# main1.net
KiCad netlist of a schematic drawn in EAGLE
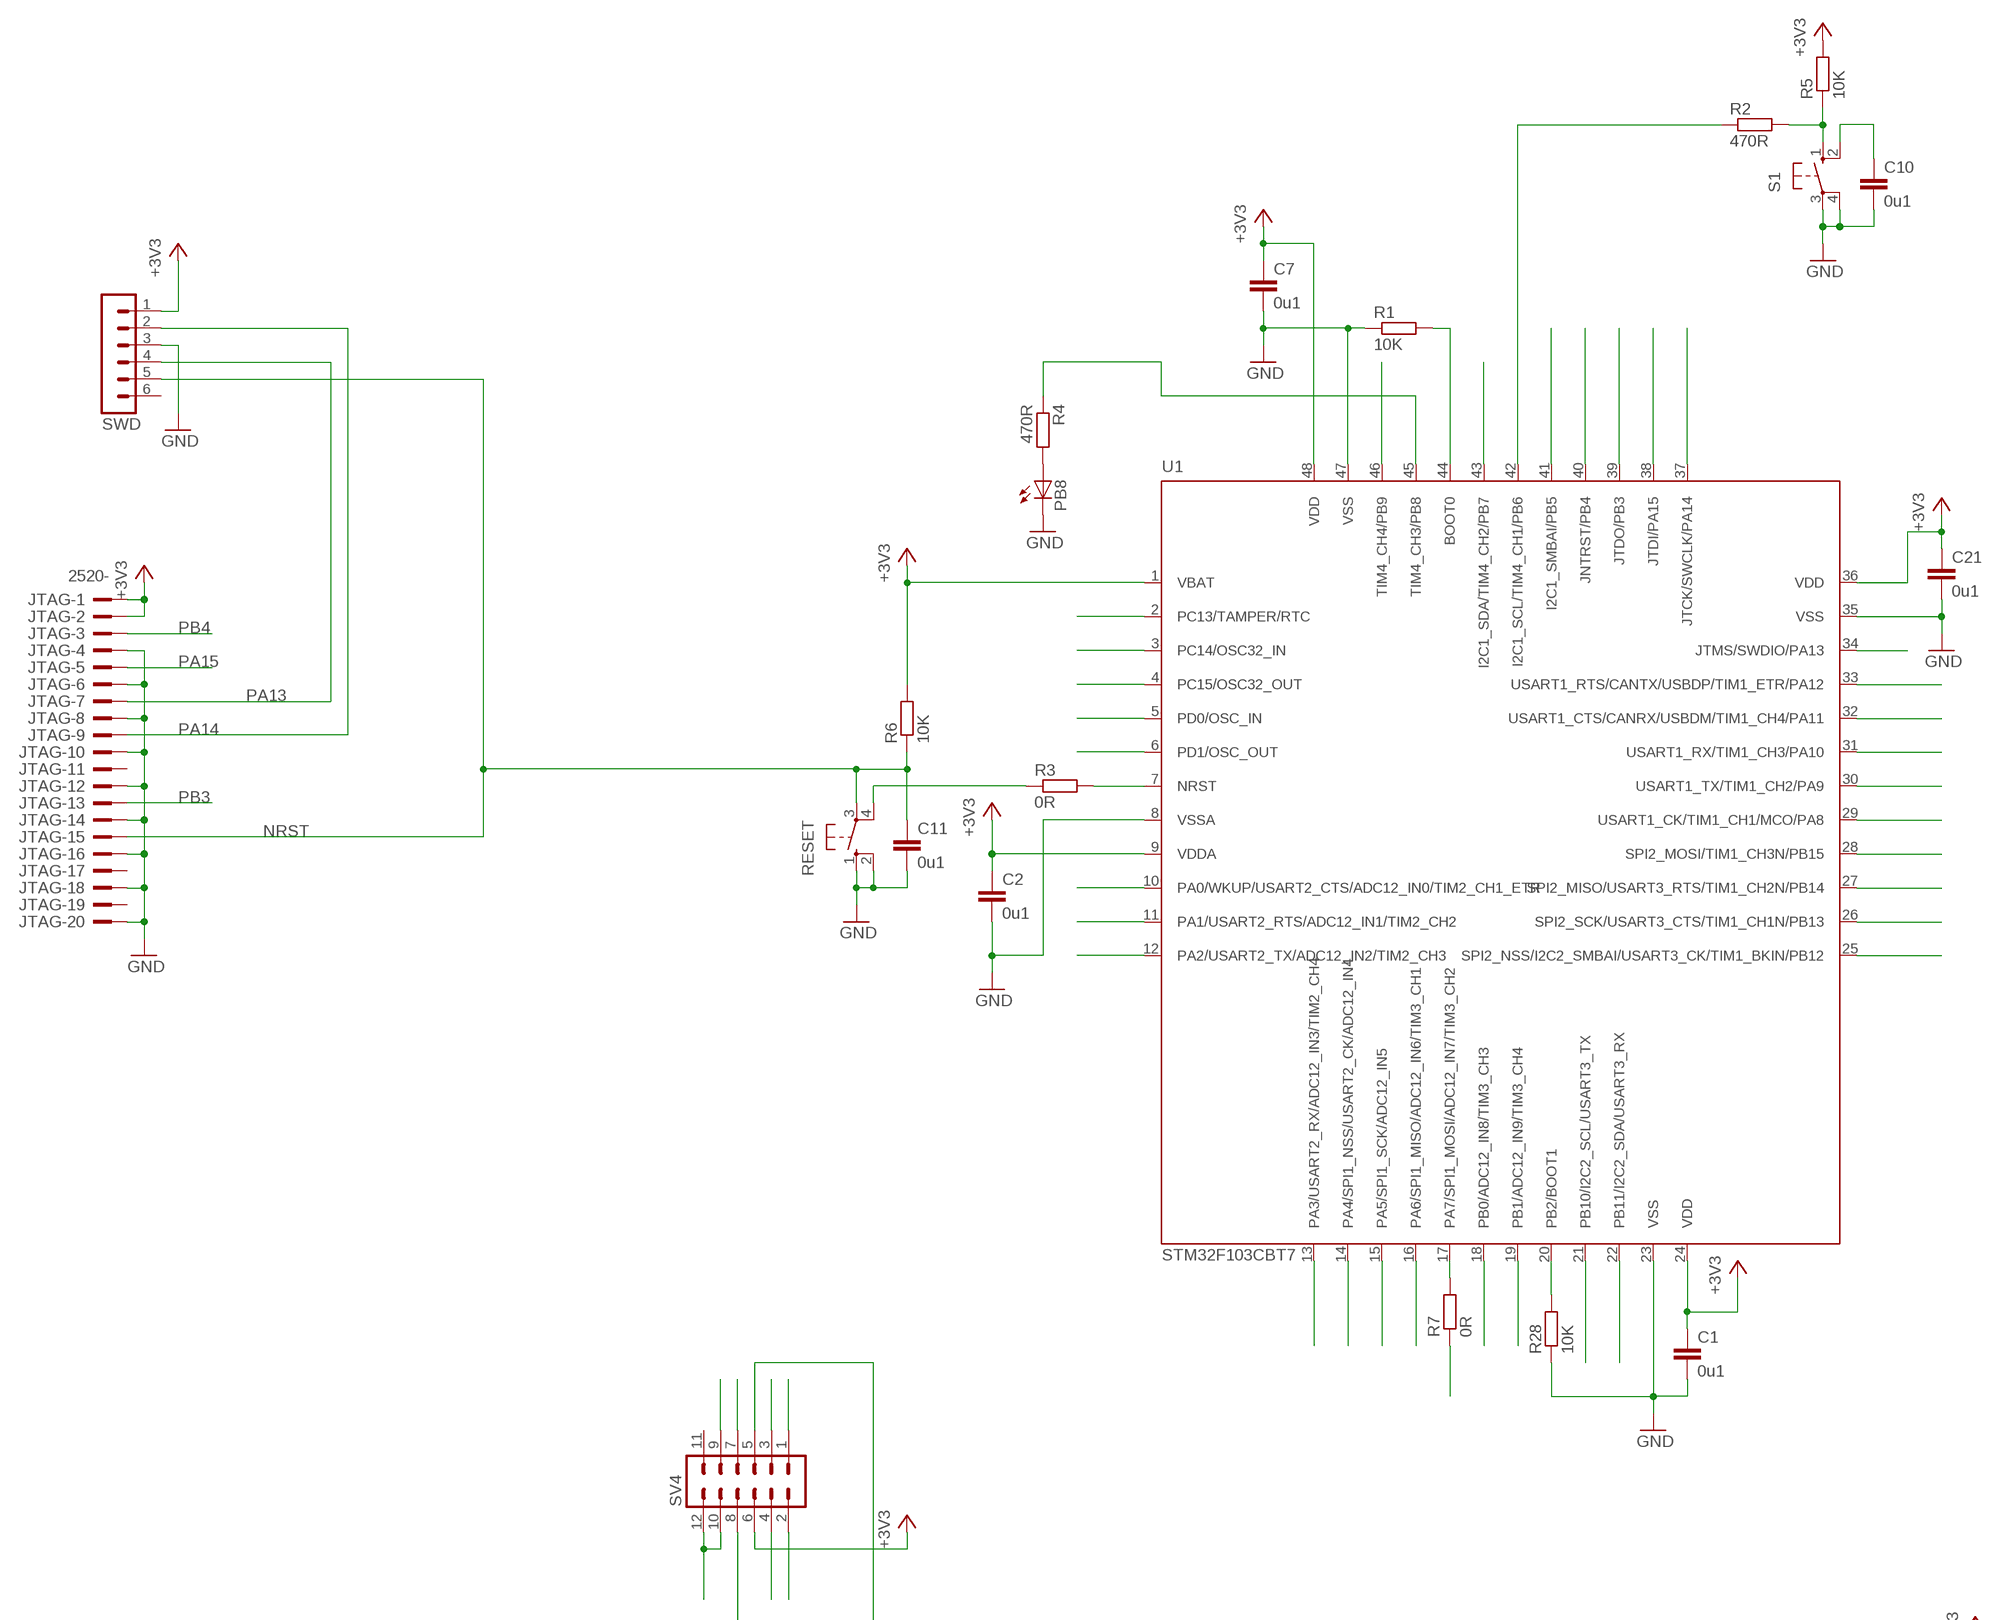
[diagram p0: schematic, sheet 1, part 1 of 2]
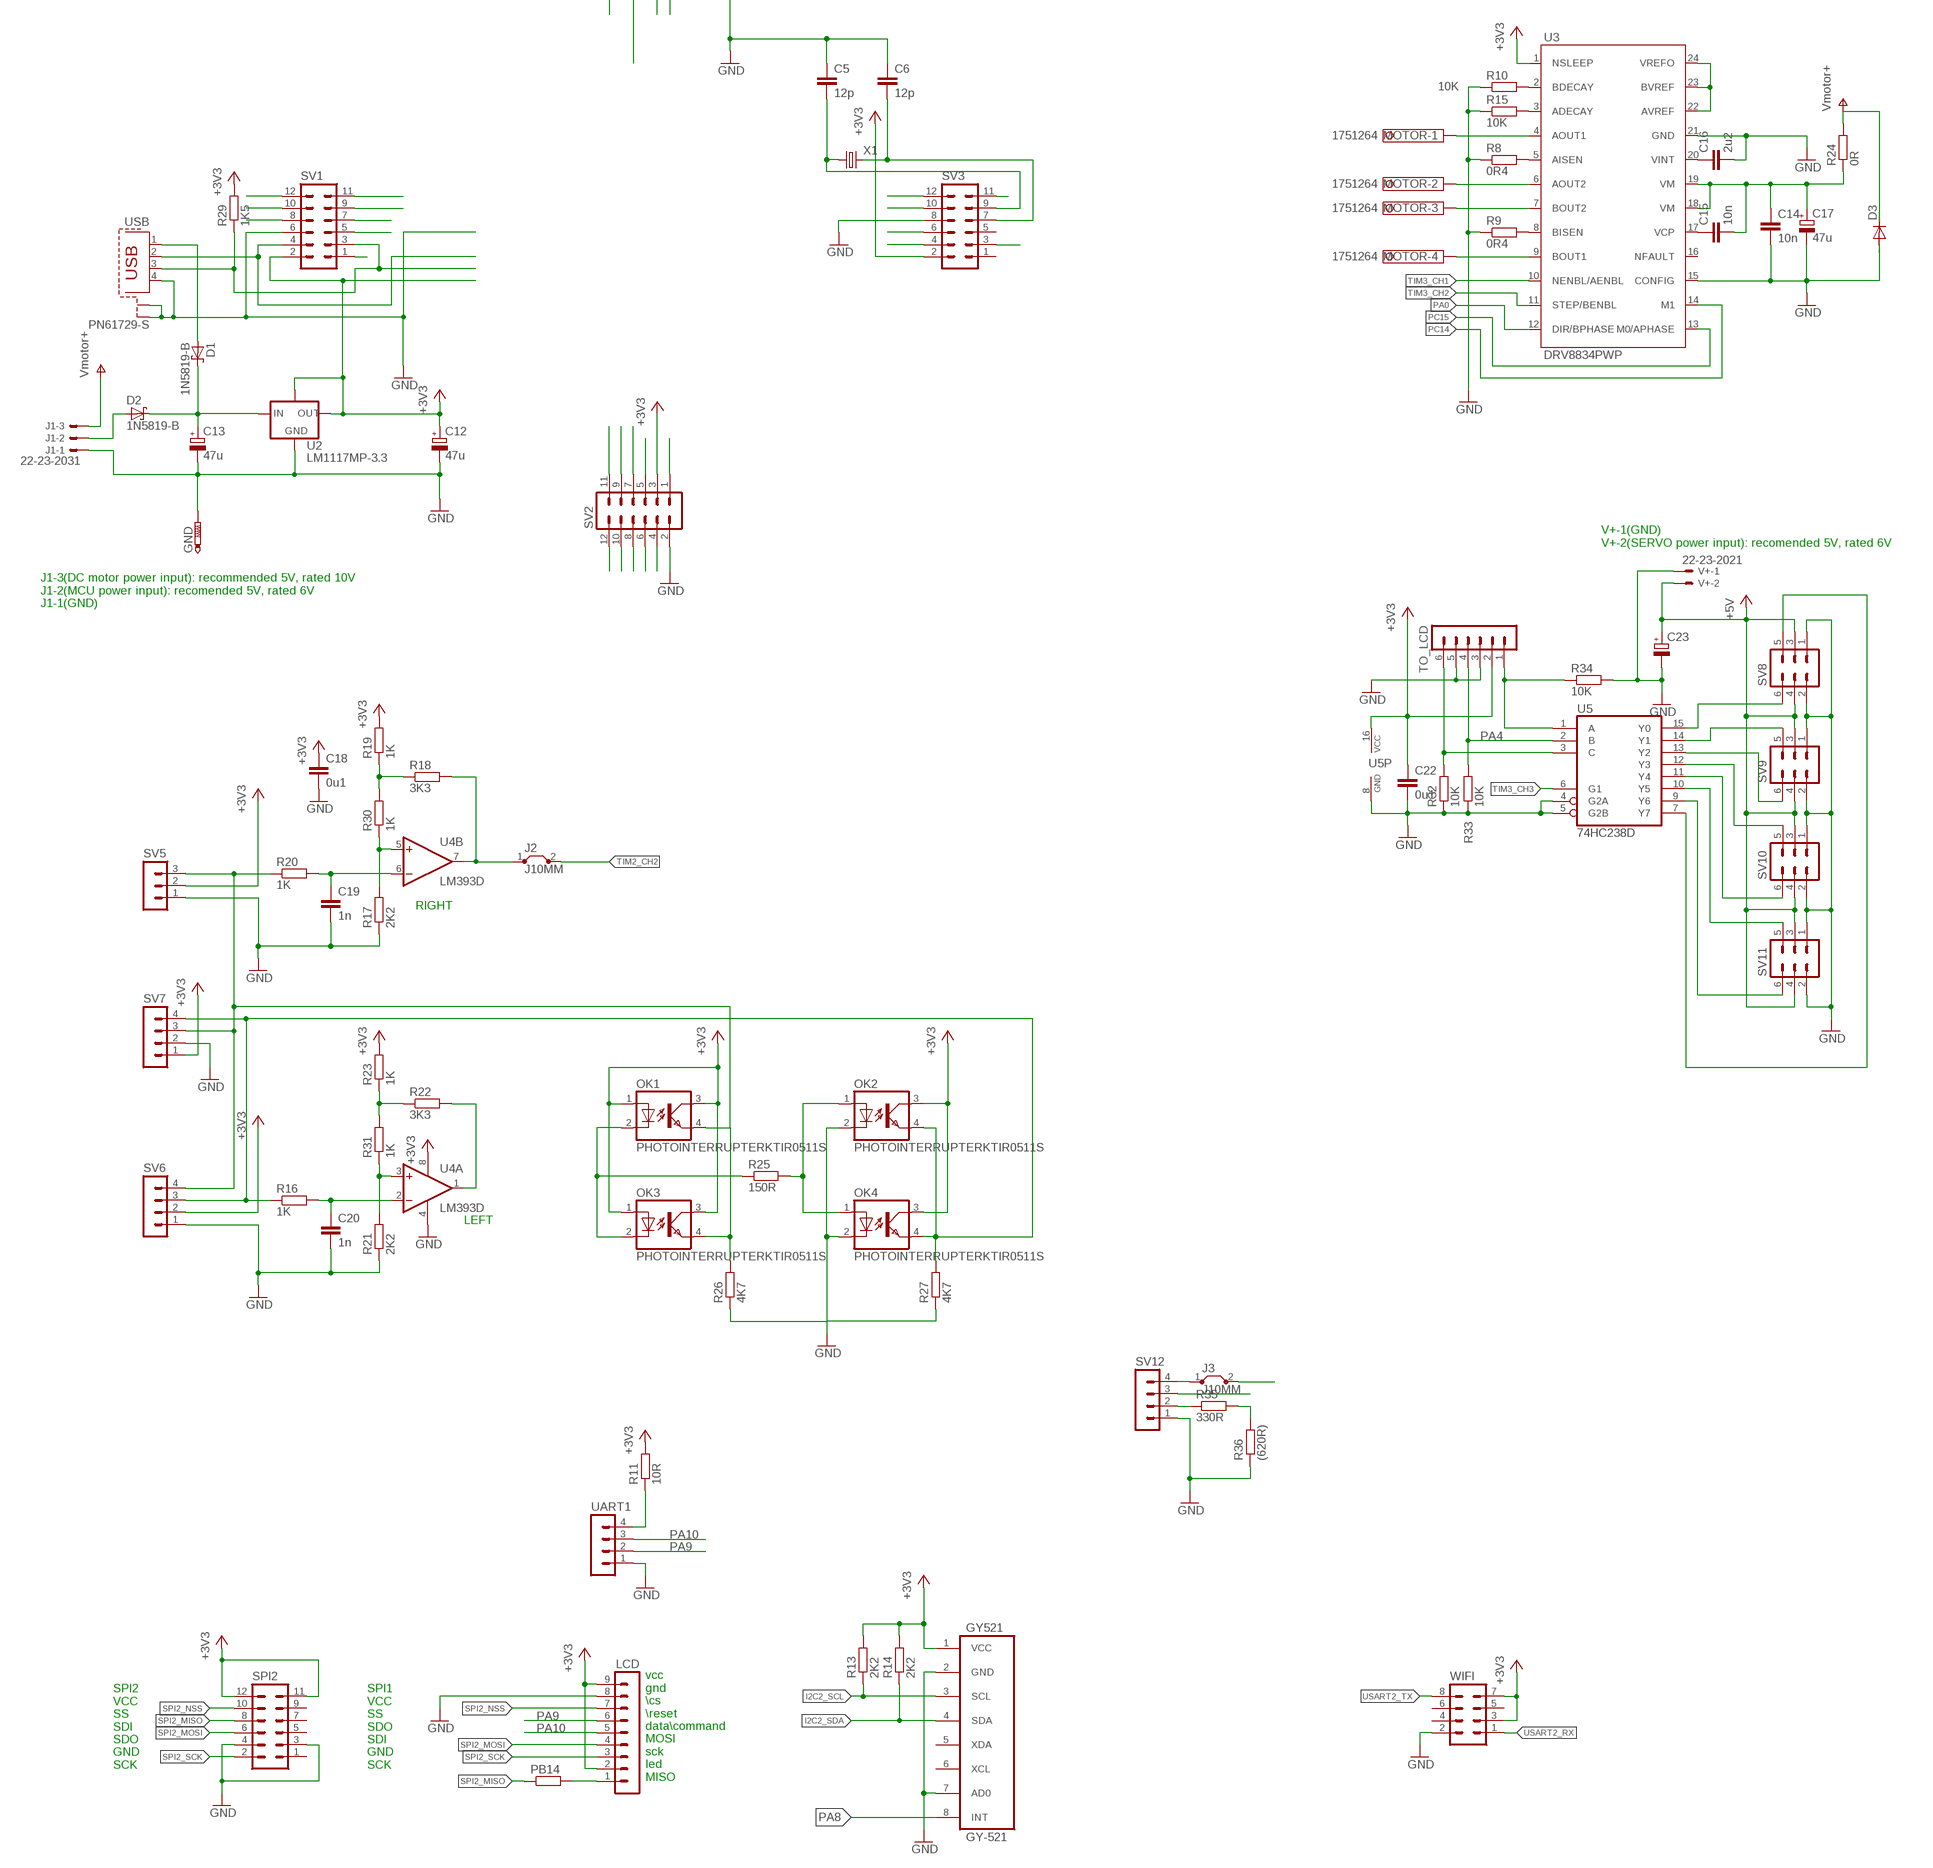
[diagram p1: schematic, sheet 1, part 2 of 2]

(export (version "E")
  (design (tool "Eeschema 10.0.6"))
  (components
    (comp (ref "C1")
      (value "0u1")
      (footprint "eagle-import:C0805")
      (libsource (lib "eagle-import") (part "C-EUC0805"))
    )
    (comp (ref "C2")
      (value "0u1")
      (footprint "eagle-import:C0805")
      (libsource (lib "eagle-import") (part "C-EUC0805"))
    )
    (comp (ref "C5")
      (value "12p")
      (footprint "eagle-import:C0805")
      (libsource (lib "eagle-import") (part "C-EUC0805"))
    )
    (comp (ref "C6")
      (value "12p")
      (footprint "eagle-import:C0805")
      (libsource (lib "eagle-import") (part "C-EUC0805"))
    )
    (comp (ref "C7")
      (value "0u1")
      (footprint "eagle-import:C0805")
      (libsource (lib "eagle-import") (part "C-EUC0805"))
    )
    (comp (ref "C10")
      (value "0u1")
      (footprint "eagle-import:C0805")
      (libsource (lib "eagle-import") (part "C-EUC0805"))
    )
    (comp (ref "C11")
      (value "0u1")
      (footprint "eagle-import:C0805")
      (libsource (lib "eagle-import") (part "C-EUC0805"))
    )
    (comp (ref "C12")
      (value "47u")
      (footprint "eagle-import:E1,8-4")
      (libsource (lib "eagle-import") (part "CPOL-EUE1.8-4"))
    )
    (comp (ref "C13")
      (value "47u")
      (footprint "eagle-import:E1,8-4")
      (libsource (lib "eagle-import") (part "CPOL-EUE1.8-4"))
    )
    (comp (ref "C14")
      (value "10n")
      (footprint "eagle-import:C0805")
      (libsource (lib "eagle-import") (part "C-EUC0805"))
    )
    (comp (ref "C15")
      (value "10n")
      (footprint "eagle-import:C0805")
      (libsource (lib "eagle-import") (part "C-EUC0805"))
    )
    (comp (ref "C16")
      (value "2u2")
      (footprint "eagle-import:C0805")
      (libsource (lib "eagle-import") (part "C-EUC0805"))
    )
    (comp (ref "C17")
      (value "47u")
      (footprint "eagle-import:E1,8-4")
      (libsource (lib "eagle-import") (part "CPOL-EUE1.8-4"))
    )
    (comp (ref "C18")
      (value "0u1")
      (footprint "eagle-import:C0805")
      (libsource (lib "eagle-import") (part "C-EUC0805"))
    )
    (comp (ref "C19")
      (value "1n")
      (footprint "eagle-import:C0805")
      (libsource (lib "eagle-import") (part "C-EUC0805"))
    )
    (comp (ref "C20")
      (value "1n")
      (footprint "eagle-import:C0805")
      (libsource (lib "eagle-import") (part "C-EUC0805"))
    )
    (comp (ref "C21")
      (value "0u1")
      (footprint "eagle-import:C0805")
      (libsource (lib "eagle-import") (part "C-EUC0805"))
    )
    (comp (ref "C22")
      (value "0u1")
      (footprint "eagle-import:C0805")
      (libsource (lib "eagle-import") (part "C-EUC0805"))
    )
    (comp (ref "C23")
      (value "CPOL-EUE2.5-7")
      (footprint "eagle-import:E2,5-7")
      (libsource (lib "eagle-import") (part "CPOL-EUE2.5-7"))
    )
    (comp (ref "D1")
      (value "1N5819-B")
      (footprint "eagle-import:DO41-7.6")
      (libsource (lib "eagle-import") (part "1N5819-B"))
    )
    (comp (ref "D2")
      (value "1N5819-B")
      (footprint "eagle-import:DO41-7.6")
      (libsource (lib "eagle-import") (part "1N5819-B"))
    )
    (comp (ref "D3")
      (value "DIODE-SMB")
      (footprint "eagle-import:SMB")
      (libsource (lib "eagle-import") (part "DIODE-SMB"))
    )
    (comp (ref "GND")
      (value "PTR1PAD1-13")
      (footprint "eagle-import:P1-13")
      (libsource (lib "eagle-import") (part "PTR1PAD1-13"))
    )
    (comp (ref "GY521")
      (value "GY-521")
      (footprint "eagle-import:GY-521")
      (libsource (lib "eagle-import") (part "GY-521"))
    )
    (comp (ref "J1")
      (value "22-23-2031")
      (footprint "eagle-import:22-23-2031")
      (fields (field (name "MF") "MOLEX"))
      (libsource (lib "eagle-import") (part "22-23-2031"))
    )
    (comp (ref "J2")
      (value "J10MM")
      (footprint "eagle-import:10")
      (libsource (lib "eagle-import") (part "J10MM"))
    )
    (comp (ref "J3")
      (value "J10MM")
      (footprint "eagle-import:10")
      (libsource (lib "eagle-import") (part "J10MM"))
    )
    (comp (ref "JTAG")
      (value "2520-")
      (footprint "eagle-import:PAK100_2500-20")
      (libsource (lib "eagle-import") (part "2520-"))
    )
    (comp (ref "LCD")
      (value "MA09-1")
      (footprint "eagle-import:MA09-1")
      (libsource (lib "eagle-import") (part "MA09-1"))
    )
    (comp (ref "MOTOR")
      (value "1751264")
      (footprint "eagle-import:1751264")
      (libsource (lib "eagle-import") (part "1751264"))
    )
    (comp (ref "OK1")
      (value "PHOTOINTERRUPTERKTIR0511S")
      (footprint "eagle-import:KTIR0511S")
      (libsource (lib "eagle-import") (part "PHOTOINTERRUPTERKTIR0511S"))
    )
    (comp (ref "OK2")
      (value "PHOTOINTERRUPTERKTIR0511S")
      (footprint "eagle-import:KTIR0511S")
      (libsource (lib "eagle-import") (part "PHOTOINTERRUPTERKTIR0511S"))
    )
    (comp (ref "OK3")
      (value "PHOTOINTERRUPTERKTIR0511S")
      (footprint "eagle-import:KTIR0511S")
      (libsource (lib "eagle-import") (part "PHOTOINTERRUPTERKTIR0511S"))
    )
    (comp (ref "OK4")
      (value "PHOTOINTERRUPTERKTIR0511S")
      (footprint "eagle-import:KTIR0511S")
      (libsource (lib "eagle-import") (part "PHOTOINTERRUPTERKTIR0511S"))
    )
    (comp (ref "PB8")
      (value "LED3MM")
      (footprint "eagle-import:LED3MM")
      (libsource (lib "eagle-import") (part "LED3MM"))
    )
    (comp (ref "PB14")
      (value "R-EU_0207/10")
      (footprint "eagle-import:0207_10")
      (libsource (lib "eagle-import") (part "R-EU_0207/10"))
    )
    (comp (ref "R1")
      (value "10K")
      (footprint "eagle-import:M0805")
      (libsource (lib "eagle-import") (part "R-EU_M0805"))
    )
    (comp (ref "R2")
      (value "470R")
      (footprint "eagle-import:0207_10")
      (libsource (lib "eagle-import") (part "R-EU_0207/10"))
    )
    (comp (ref "R3")
      (value "0R")
      (footprint "eagle-import:0207_10")
      (libsource (lib "eagle-import") (part "R-EU_0207/10"))
    )
    (comp (ref "R4")
      (value "470R")
      (footprint "eagle-import:0207_10")
      (libsource (lib "eagle-import") (part "R-EU_0207/10"))
    )
    (comp (ref "R5")
      (value "10K")
      (footprint "eagle-import:0207_10")
      (libsource (lib "eagle-import") (part "R-EU_0207/10"))
    )
    (comp (ref "R6")
      (value "10K")
      (footprint "eagle-import:M0805")
      (libsource (lib "eagle-import") (part "R-EU_M0805"))
    )
    (comp (ref "R7")
      (value "0R")
      (footprint "eagle-import:0207_10")
      (libsource (lib "eagle-import") (part "R-EU_0207/10"))
    )
    (comp (ref "R8")
      (value "0R4")
      (footprint "eagle-import:R2010")
      (libsource (lib "eagle-import") (part "R-EU_R2010"))
    )
    (comp (ref "R9")
      (value "0R4")
      (footprint "eagle-import:R2010")
      (libsource (lib "eagle-import") (part "R-EU_R2010"))
    )
    (comp (ref "R10")
      (value "10K")
      (footprint "eagle-import:R0805")
      (libsource (lib "eagle-import") (part "R-EU_R0805"))
    )
    (comp (ref "R11")
      (value "10R")
      (footprint "eagle-import:M0805")
      (libsource (lib "eagle-import") (part "R-EU_M0805"))
    )
    (comp (ref "R13")
      (value "2K2")
      (footprint "eagle-import:M0805")
      (libsource (lib "eagle-import") (part "R-EU_M0805"))
    )
    (comp (ref "R14")
      (value "2K2")
      (footprint "eagle-import:M0805")
      (libsource (lib "eagle-import") (part "R-EU_M0805"))
    )
    (comp (ref "R15")
      (value "10K")
      (footprint "eagle-import:R0805")
      (libsource (lib "eagle-import") (part "R-EU_R0805"))
    )
    (comp (ref "R16")
      (value "1K")
      (footprint "eagle-import:0207_10")
      (libsource (lib "eagle-import") (part "R-EU_0207/10"))
    )
    (comp (ref "R17")
      (value "2K2")
      (footprint "eagle-import:M0805")
      (libsource (lib "eagle-import") (part "R-EU_M0805"))
    )
    (comp (ref "R18")
      (value "3K3")
      (footprint "eagle-import:M0805")
      (libsource (lib "eagle-import") (part "R-EU_M0805"))
    )
    (comp (ref "R19")
      (value "1K")
      (footprint "eagle-import:M0805")
      (libsource (lib "eagle-import") (part "R-EU_M0805"))
    )
    (comp (ref "R20")
      (value "1K")
      (footprint "eagle-import:0207_10")
      (libsource (lib "eagle-import") (part "R-EU_0207/10"))
    )
    (comp (ref "R21")
      (value "2K2")
      (footprint "eagle-import:M0805")
      (libsource (lib "eagle-import") (part "R-EU_M0805"))
    )
    (comp (ref "R22")
      (value "3K3")
      (footprint "eagle-import:M0805")
      (libsource (lib "eagle-import") (part "R-EU_M0805"))
    )
    (comp (ref "R23")
      (value "1K")
      (footprint "eagle-import:M0805")
      (libsource (lib "eagle-import") (part "R-EU_M0805"))
    )
    (comp (ref "R24")
      (value "0R")
      (footprint "eagle-import:0207_10")
      (libsource (lib "eagle-import") (part "R-EU_0207/10"))
    )
    (comp (ref "R25")
      (value "150R")
      (footprint "eagle-import:0207_10")
      (libsource (lib "eagle-import") (part "R-EU_0207/10"))
    )
    (comp (ref "R26")
      (value "4K7")
      (footprint "eagle-import:M0805")
      (libsource (lib "eagle-import") (part "R-EU_M0805"))
    )
    (comp (ref "R27")
      (value "4K7")
      (footprint "eagle-import:M0805")
      (libsource (lib "eagle-import") (part "R-EU_M0805"))
    )
    (comp (ref "R28")
      (value "10K")
      (footprint "eagle-import:M0805")
      (libsource (lib "eagle-import") (part "R-EU_M0805"))
    )
    (comp (ref "R29")
      (value "1K5")
      (footprint "eagle-import:M0805")
      (libsource (lib "eagle-import") (part "R-EU_M0805"))
    )
    (comp (ref "R30")
      (value "1K")
      (footprint "eagle-import:M0805")
      (libsource (lib "eagle-import") (part "R-EU_M0805"))
    )
    (comp (ref "R31")
      (value "1K")
      (footprint "eagle-import:M0805")
      (libsource (lib "eagle-import") (part "R-EU_M0805"))
    )
    (comp (ref "R32")
      (value "10K")
      (footprint "eagle-import:M0805")
      (libsource (lib "eagle-import") (part "R-EU_M0805"))
    )
    (comp (ref "R33")
      (value "10K")
      (footprint "eagle-import:M0805")
      (libsource (lib "eagle-import") (part "R-EU_M0805"))
    )
    (comp (ref "R34")
      (value "10K")
      (footprint "eagle-import:M0805")
      (libsource (lib "eagle-import") (part "R-EU_M0805"))
    )
    (comp (ref "R35")
      (value "330R")
      (footprint "eagle-import:M0805")
      (libsource (lib "eagle-import") (part "R-EU_M0805"))
    )
    (comp (ref "R36")
      (value "(620R)")
      (footprint "eagle-import:M0805")
      (libsource (lib "eagle-import") (part "R-EU_M0805"))
    )
    (comp (ref "RESET")
      (value "10-XX")
      (footprint "eagle-import:B3F-10XX")
      (fields (field (name "MPN") "B3F-1000"))
      (libsource (lib "eagle-import") (part "10-XX"))
    )
    (comp (ref "S1")
      (value "10-XX")
      (footprint "eagle-import:B3F-10XX")
      (fields (field (name "MPN") "B3F-1000"))
      (libsource (lib "eagle-import") (part "10-XX"))
    )
    (comp (ref "SPI2")
      (value "MA06-2")
      (footprint "eagle-import:MA06-2")
      (libsource (lib "eagle-import") (part "MA06-2"))
    )
    (comp (ref "SV1")
      (value "MA06-2")
      (footprint "eagle-import:MA06-2")
      (libsource (lib "eagle-import") (part "MA06-2"))
    )
    (comp (ref "SV2")
      (value "MA06-2")
      (footprint "eagle-import:MA06-2")
      (libsource (lib "eagle-import") (part "MA06-2"))
    )
    (comp (ref "SV3")
      (value "MA06-2")
      (footprint "eagle-import:MA06-2")
      (libsource (lib "eagle-import") (part "MA06-2"))
    )
    (comp (ref "SV4")
      (value "MA06-2")
      (footprint "eagle-import:MA06-2")
      (libsource (lib "eagle-import") (part "MA06-2"))
    )
    (comp (ref "SV5")
      (value "MA03-1")
      (footprint "eagle-import:MA03-1")
      (libsource (lib "eagle-import") (part "MA03-1"))
    )
    (comp (ref "SV6")
      (value "MA04-1")
      (footprint "eagle-import:MA04-1")
      (libsource (lib "eagle-import") (part "MA04-1"))
    )
    (comp (ref "SV7")
      (value "MA04-1")
      (footprint "eagle-import:MA04-1")
      (libsource (lib "eagle-import") (part "MA04-1"))
    )
    (comp (ref "SV8")
      (value "MA03-2")
      (footprint "eagle-import:MA03-2")
      (libsource (lib "eagle-import") (part "MA03-2"))
    )
    (comp (ref "SV9")
      (value "MA03-2")
      (footprint "eagle-import:MA03-2")
      (libsource (lib "eagle-import") (part "MA03-2"))
    )
    (comp (ref "SV10")
      (value "MA03-2")
      (footprint "eagle-import:MA03-2")
      (libsource (lib "eagle-import") (part "MA03-2"))
    )
    (comp (ref "SV11")
      (value "MA03-2")
      (footprint "eagle-import:MA03-2")
      (libsource (lib "eagle-import") (part "MA03-2"))
    )
    (comp (ref "SV12")
      (value "MA04-1")
      (footprint "eagle-import:MA04-1")
      (libsource (lib "eagle-import") (part "MA04-1"))
    )
    (comp (ref "SWD")
      (value "MA06-1")
      (footprint "eagle-import:MA06-1")
      (libsource (lib "eagle-import") (part "MA06-1"))
    )
    (comp (ref "TO_LCD")
      (value "MA06-1")
      (footprint "eagle-import:MA06-1")
      (libsource (lib "eagle-import") (part "MA06-1"))
    )
    (comp (ref "U1")
      (value "STM32F103CBT7")
      (footprint "eagle-import:LQFP48-7X7")
      (libsource (lib "eagle-import") (part "STM32F103CBT7"))
    )
    (comp (ref "U2")
      (value "LM1117MP-3.3")
      (footprint "eagle-import:SOT230P700X180-4N")
      (libsource (lib "eagle-import") (part "LM1117"))
    )
    (comp (ref "U3")
      (value "DRV8834PWP")
      (footprint "eagle-import:PWP-TSSOP24")
      (libsource (lib "eagle-import") (part "DRV8834PWP"))
    )
    (comp (ref "U4")
      (value "LM393D")
      (footprint "eagle-import:SO08")
      (libsource (lib "eagle-import") (part "LM393D"))
    )
    (comp (ref "U5")
      (value "74HC238D")
      (footprint "eagle-import:SO16")
      (libsource (lib "eagle-import") (part "74238DHC"))
    )
    (comp (ref "UART1")
      (value "MA04-1")
      (footprint "eagle-import:MA04-1")
      (libsource (lib "eagle-import") (part "MA04-1"))
    )
    (comp (ref "USB")
      (value "PN61729-S")
      (footprint "eagle-import:PN61729-S")
      (libsource (lib "eagle-import") (part "PN61729-S"))
    )
    (comp (ref "V+")
      (value "22-23-2021")
      (footprint "eagle-import:22-23-2021")
      (fields (field (name "MF") "MOLEX"))
      (libsource (lib "eagle-import") (part "22-23-2021"))
    )
    (comp (ref "WIFI")
      (value "MA04-2")
      (footprint "eagle-import:MA04-2")
      (libsource (lib "eagle-import") (part "MA04-2"))
    )
    (comp (ref "X1")
      (value "CRYSTALHC49S")
      (footprint "eagle-import:HC49_S")
      (libsource (lib "eagle-import") (part "CRYSTALHC49S"))
    )
  )
  (nets
    (net (code "1") (name "+3V3") (class "Default")
      (node (ref "C1") (pin "1") (pinfunction "1_1") (pintype "passive"))
      (node (ref "C12") (pin "+") (pinfunction "+_+") (pintype "passive"))
      (node (ref "C18") (pin "1") (pinfunction "1_1") (pintype "passive"))
      (node (ref "C2") (pin "1") (pinfunction "1_1") (pintype "passive"))
      (node (ref "C21") (pin "1") (pinfunction "1_1") (pintype "passive"))
      (node (ref "C22") (pin "1") (pinfunction "1_1") (pintype "passive"))
      (node (ref "C7") (pin "1") (pinfunction "1_1") (pintype "passive"))
      (node (ref "GY521") (pin "1") (pinfunction "VCC_1") (pintype "power_in"))
      (node (ref "JTAG") (pin "1") (pinfunction "KL_1") (pintype "passive"))
      (node (ref "JTAG") (pin "2") (pinfunction "KL_2") (pintype "passive"))
      (node (ref "LCD") (pin "2") (pinfunction "2_2") (pintype "passive"))
      (node (ref "LCD") (pin "9") (pinfunction "9_9") (pintype "passive"))
      (node (ref "OK1") (pin "1") (pinfunction "A_1") (pintype "passive"))
      (node (ref "OK1") (pin "3") (pinfunction "COL_3") (pintype "passive"))
      (node (ref "OK2") (pin "3") (pinfunction "COL_3") (pintype "passive"))
      (node (ref "OK3") (pin "1") (pinfunction "A_1") (pintype "passive"))
      (node (ref "OK3") (pin "3") (pinfunction "COL_3") (pintype "passive"))
      (node (ref "OK4") (pin "3") (pinfunction "COL_3") (pintype "passive"))
      (node (ref "R11") (pin "2") (pinfunction "2_2") (pintype "passive"))
      (node (ref "R13") (pin "2") (pinfunction "2_2") (pintype "passive"))
      (node (ref "R14") (pin "2") (pinfunction "2_2") (pintype "passive"))
      (node (ref "R19") (pin "2") (pinfunction "2_2") (pintype "passive"))
      (node (ref "R23") (pin "2") (pinfunction "2_2") (pintype "passive"))
      (node (ref "R29") (pin "2") (pinfunction "2_2") (pintype "passive"))
      (node (ref "R5") (pin "2") (pinfunction "2_2") (pintype "passive"))
      (node (ref "R6") (pin "2") (pinfunction "2_2") (pintype "passive"))
      (node (ref "SPI2") (pin "11") (pinfunction "11_11") (pintype "passive"))
      (node (ref "SPI2") (pin "12") (pinfunction "12_12") (pintype "passive"))
      (node (ref "SV1") (pin "2") (pinfunction "2_2") (pintype "passive"))
      (node (ref "SV2") (pin "3") (pinfunction "3_3") (pintype "passive"))
      (node (ref "SV3") (pin "2") (pinfunction "2_2") (pintype "passive"))
      (node (ref "SV4") (pin "6") (pinfunction "6_6") (pintype "passive"))
      (node (ref "SV5") (pin "2") (pinfunction "2_2") (pintype "passive"))
      (node (ref "SV6") (pin "2") (pinfunction "2_2") (pintype "passive"))
      (node (ref "SV7") (pin "1") (pinfunction "1_1") (pintype "passive"))
      (node (ref "SWD") (pin "1") (pinfunction "1_1") (pintype "passive"))
      (node (ref "TO_LCD") (pin "2") (pinfunction "2_2") (pintype "passive"))
      (node (ref "U1") (pin "1") (pinfunction "VBAT_1") (pintype "input"))
      (node (ref "U1") (pin "24") (pinfunction "VDD_24") (pintype "power_in"))
      (node (ref "U1") (pin "36") (pinfunction "VDD_36") (pintype "power_in"))
      (node (ref "U1") (pin "48") (pinfunction "VDD_48") (pintype "power_in"))
      (node (ref "U1") (pin "9") (pinfunction "VDDA_9") (pintype "power_in"))
      (node (ref "U2") (pin "2") (pinfunction "OUT_2") (pintype "passive"))
      (node (ref "U2") (pin "4") (pinfunction "TAB_4") (pintype "passive"))
      (node (ref "U3") (pin "1") (pinfunction "NSLEEP_1") (pintype "passive"))
      (node (ref "U4") (pin "8") (pinfunction "V+_8") (pintype "power_in"))
      (node (ref "U5") (pin "16") (pinfunction "VCC_16") (pintype "power_in"))
      (node (ref "WIFI") (pin "3") (pinfunction "3_3") (pintype "passive"))
      (node (ref "WIFI") (pin "7") (pinfunction "7_7") (pintype "passive"))
    )
    (net (code "2") (name "+5V") (class "Default")
      (node (ref "C23") (pin "+") (pinfunction "+_+") (pintype "passive"))
      (node (ref "SV10") (pin "3") (pinfunction "3_3") (pintype "passive"))
      (node (ref "SV10") (pin "4") (pinfunction "4_4") (pintype "passive"))
      (node (ref "SV11") (pin "3") (pinfunction "3_3") (pintype "passive"))
      (node (ref "SV11") (pin "4") (pinfunction "4_4") (pintype "passive"))
      (node (ref "SV8") (pin "3") (pinfunction "3_3") (pintype "passive"))
      (node (ref "SV8") (pin "4") (pinfunction "4_4") (pintype "passive"))
      (node (ref "SV9") (pin "3") (pinfunction "3_3") (pintype "passive"))
      (node (ref "SV9") (pin "4") (pinfunction "4_4") (pintype "passive"))
      (node (ref "V+") (pin "2") (pinfunction "S_2") (pintype "passive"))
    )
    (net (code "3") (name "/BOOT0") (class "Default")
      (node (ref "R1") (pin "2") (pinfunction "2_2") (pintype "passive"))
      (node (ref "SV2") (pin "5") (pinfunction "5_5") (pintype "passive"))
      (node (ref "U1") (pin "44") (pinfunction "BOOT0_44") (pintype "input"))
    )
    (net (code "4") (name "/BOOT1") (class "Default")
      (node (ref "R28") (pin "2") (pinfunction "2_2") (pintype "passive"))
      (node (ref "SV4") (pin "8") (pinfunction "8_8") (pintype "passive"))
      (node (ref "U1") (pin "20") (pinfunction "PB2/BOOT1_20") (pintype "bidirectional"))
    )
    (net (code "5") (name "/N$13") (class "Default")
      (node (ref "D2") (pin "A") (pinfunction "A_A") (pintype "passive"))
      (node (ref "J1") (pin "2") (pinfunction "S_2") (pintype "passive"))
      (node (ref "J3") (pin "2") (pinfunction "2_2") (pintype "passive"))
    )
    (net (code "6") (name "/NRST") (class "Default")
      (node (ref "C11") (pin "1") (pinfunction "1_1") (pintype "passive"))
      (node (ref "JTAG") (pin "15") (pinfunction "KL_15") (pintype "passive"))
      (node (ref "R6") (pin "1") (pinfunction "1_1") (pintype "passive"))
      (node (ref "RESET") (pin "3") (pinfunction "P_3") (pintype "passive"))
      (node (ref "SWD") (pin "5") (pinfunction "5_5") (pintype "passive"))
    )
    (net (code "7") (name "/PA4") (class "Default")
      (node (ref "R33") (pin "2") (pinfunction "2_2") (pintype "passive"))
      (node (ref "SV4") (pin "1") (pinfunction "1_1") (pintype "passive"))
      (node (ref "TO_LCD") (pin "4") (pinfunction "4_4") (pintype "passive"))
      (node (ref "U1") (pin "14") (pinfunction "PA4/SPI1_NSS/USART2_CK/ADC12_IN4_14") (pintype "bidirectional"))
      (node (ref "U5") (pin "2") (pinfunction "B_2") (pintype "input"))
    )
    (net (code "8") (name "/PA5") (class "Default")
      (node (ref "SV4") (pin "2") (pinfunction "2_2") (pintype "passive"))
      (node (ref "U1") (pin "15") (pinfunction "PA5/SPI1_SCK/ADC12_IN5_15") (pintype "bidirectional"))
    )
    (net (code "9") (name "/PA9") (class "Default")
      (node (ref "LCD") (pin "6") (pinfunction "6_6") (pintype "passive"))
      (node (ref "SV1") (pin "8") (pinfunction "8_8") (pintype "passive"))
      (node (ref "U1") (pin "30") (pinfunction "USART1_TX/TIM1_CH2/PA9_30") (pintype "bidirectional"))
      (node (ref "UART1") (pin "2") (pinfunction "2_2") (pintype "passive"))
    )
    (net (code "10") (name "/PA10") (class "Default")
      (node (ref "LCD") (pin "5") (pinfunction "5_5") (pintype "passive"))
      (node (ref "SV1") (pin "5") (pinfunction "5_5") (pintype "passive"))
      (node (ref "U1") (pin "31") (pinfunction "USART1_RX/TIM1_CH3/PA10_31") (pintype "bidirectional"))
      (node (ref "UART1") (pin "3") (pinfunction "3_3") (pintype "passive"))
    )
    (net (code "11") (name "/PA13") (class "Default")
      (node (ref "JTAG") (pin "7") (pinfunction "KL_7") (pintype "passive"))
      (node (ref "SV1") (pin "1") (pinfunction "1_1") (pintype "passive"))
      (node (ref "SWD") (pin "4") (pinfunction "4_4") (pintype "passive"))
      (node (ref "U1") (pin "34") (pinfunction "JTMS/SWDIO/PA13_34") (pintype "bidirectional"))
    )
    (net (code "12") (name "/PA14") (class "Default")
      (node (ref "JTAG") (pin "9") (pinfunction "KL_9") (pintype "passive"))
      (node (ref "SV2") (pin "12") (pinfunction "12_12") (pintype "passive"))
      (node (ref "SWD") (pin "2") (pinfunction "2_2") (pintype "passive"))
      (node (ref "U1") (pin "37") (pinfunction "JTCK/SWCLK/PA14_37") (pintype "bidirectional"))
    )
    (net (code "13") (name "/PA15") (class "Default")
      (node (ref "JTAG") (pin "5") (pinfunction "KL_5") (pintype "passive"))
      (node (ref "SV2") (pin "11") (pinfunction "11_11") (pintype "passive"))
      (node (ref "U1") (pin "38") (pinfunction "JTDI/PA15_38") (pintype "bidirectional"))
    )
    (net (code "14") (name "/PB1") (class "Default")
      (node (ref "SV4") (pin "7") (pinfunction "7_7") (pintype "passive"))
      (node (ref "U1") (pin "19") (pinfunction "PB1/ADC12_IN9/TIM3_CH4_19") (pintype "bidirectional"))
    )
    (net (code "15") (name "/PB3") (class "Default")
      (node (ref "JTAG") (pin "13") (pinfunction "KL_13") (pintype "passive"))
      (node (ref "SV2") (pin "10") (pinfunction "10_10") (pintype "passive"))
      (node (ref "U1") (pin "39") (pinfunction "JTDO/PB3_39") (pintype "bidirectional"))
    )
    (net (code "16") (name "/PB4") (class "Default")
      (node (ref "JTAG") (pin "3") (pinfunction "KL_3") (pintype "passive"))
      (node (ref "R35") (pin "2") (pinfunction "2_2") (pintype "passive"))
      (node (ref "R36") (pin "2") (pinfunction "2_2") (pintype "passive"))
      (node (ref "SV2") (pin "9") (pinfunction "9_9") (pintype "passive"))
      (node (ref "U1") (pin "40") (pinfunction "JNTRST/PB4_40") (pintype "bidirectional"))
    )
    (net (code "17") (name "/PB5") (class "Default")
      (node (ref "SV12") (pin "3") (pinfunction "3_3") (pintype "passive"))
      (node (ref "SV2") (pin "8") (pinfunction "8_8") (pintype "passive"))
      (node (ref "U1") (pin "41") (pinfunction "I2C1_SMBAI/PB5_41") (pintype "bidirectional"))
    )
    (net (code "18") (name "/PB6") (class "Default")
      (node (ref "R2") (pin "1") (pinfunction "1_1") (pintype "passive"))
      (node (ref "SV2") (pin "7") (pinfunction "7_7") (pintype "passive"))
      (node (ref "U1") (pin "42") (pinfunction "I2C1_SCL/TIM4_CH1/PB6_42") (pintype "bidirectional"))
    )
    (net (code "19") (name "/PB7") (class "Default")
      (node (ref "R22") (pin "2") (pinfunction "2_2") (pintype "passive"))
      (node (ref "SV2") (pin "6") (pinfunction "6_6") (pintype "passive"))
      (node (ref "U1") (pin "43") (pinfunction "I2C1_SDA/TIM4_CH2/PB7_43") (pintype "bidirectional"))
      (node (ref "U4") (pin "1") (pinfunction "OUT_1") (pintype "output"))
    )
    (net (code "20") (name "/PB8") (class "Default")
      (node (ref "R4") (pin "1") (pinfunction "1_1") (pintype "passive"))
      (node (ref "SV2") (pin "4") (pinfunction "4_4") (pintype "passive"))
      (node (ref "U1") (pin "45") (pinfunction "TIM4_CH3/PB8_45") (pintype "bidirectional"))
    )
    (net (code "21") (name "/PC13") (class "Default")
      (node (ref "SV3") (pin "4") (pinfunction "4_4") (pintype "passive"))
      (node (ref "U1") (pin "2") (pinfunction "PC13/TAMPER/RTC_2") (pintype "bidirectional"))
    )
    (net (code "22") (name "/PD0") (class "Default")
      (node (ref "C6") (pin "2") (pinfunction "2_2") (pintype "passive"))
      (node (ref "SV3") (pin "7") (pinfunction "7_7") (pintype "passive"))
      (node (ref "U1") (pin "5") (pinfunction "PD0/OSC_IN_5") (pintype "bidirectional"))
      (node (ref "X1") (pin "2") (pinfunction "2_2") (pintype "passive"))
    )
    (net (code "23") (name "/PD1") (class "Default")
      (node (ref "C5") (pin "2") (pinfunction "2_2") (pintype "passive"))
      (node (ref "SV3") (pin "9") (pinfunction "9_9") (pintype "passive"))
      (node (ref "U1") (pin "6") (pinfunction "PD1/OSC_OUT_6") (pintype "bidirectional"))
      (node (ref "X1") (pin "1") (pinfunction "1_1") (pintype "passive"))
    )
    (net (code "24") (name "/TIM4_CH4") (class "Default")
      (node (ref "SV2") (pin "1") (pinfunction "1_1") (pintype "passive"))
      (node (ref "U1") (pin "46") (pinfunction "TIM4_CH4/PB9_46") (pintype "bidirectional"))
    )
    (net (code "25") (name "/USBDM") (class "Default")
      (node (ref "SV1") (pin "4") (pinfunction "4_4") (pintype "passive"))
      (node (ref "U1") (pin "32") (pinfunction "USART1_CTS/CANRX/USBDM/TIM1_CH4/PA11_32") (pintype "bidirectional"))
      (node (ref "USB") (pin "2") (pinfunction "2_2") (pintype "passive"))
    )
    (net (code "26") (name "/USBDP") (class "Default")
      (node (ref "R29") (pin "1") (pinfunction "1_1") (pintype "passive"))
      (node (ref "SV1") (pin "3") (pinfunction "3_3") (pintype "passive"))
      (node (ref "U1") (pin "33") (pinfunction "USART1_RTS/CANTX/USBDP/TIM1_ETR/PA12_33") (pintype "bidirectional"))
      (node (ref "USB") (pin "3") (pinfunction "3_3") (pintype "passive"))
    )
    (net (code "27") (name "GND") (class "Default")
      (node (ref "C1") (pin "2") (pinfunction "2_2") (pintype "passive"))
      (node (ref "C10") (pin "2") (pinfunction "2_2") (pintype "passive"))
      (node (ref "C11") (pin "2") (pinfunction "2_2") (pintype "passive"))
      (node (ref "C12") (pin "-") (pinfunction "-_-") (pintype "passive"))
      (node (ref "C13") (pin "-") (pinfunction "-_-") (pintype "passive"))
      (node (ref "C14") (pin "2") (pinfunction "2_2") (pintype "passive"))
      (node (ref "C16") (pin "2") (pinfunction "2_2") (pintype "passive"))
      (node (ref "C17") (pin "-") (pinfunction "-_-") (pintype "passive"))
      (node (ref "C18") (pin "2") (pinfunction "2_2") (pintype "passive"))
      (node (ref "C19") (pin "2") (pinfunction "2_2") (pintype "passive"))
      (node (ref "C2") (pin "2") (pinfunction "2_2") (pintype "passive"))
      (node (ref "C20") (pin "2") (pinfunction "2_2") (pintype "passive"))
      (node (ref "C21") (pin "2") (pinfunction "2_2") (pintype "passive"))
      (node (ref "C22") (pin "2") (pinfunction "2_2") (pintype "passive"))
      (node (ref "C23") (pin "-") (pinfunction "-_-") (pintype "passive"))
      (node (ref "C5") (pin "1") (pinfunction "1_1") (pintype "passive"))
      (node (ref "C6") (pin "1") (pinfunction "1_1") (pintype "passive"))
      (node (ref "C7") (pin "2") (pinfunction "2_2") (pintype "passive"))
      (node (ref "D3") (pin "A") (pinfunction "A_A") (pintype "passive"))
      (node (ref "GND") (pin "TP") (pinfunction "TP_TP") (pintype "input"))
      (node (ref "GY521") (pin "2") (pinfunction "GND_2") (pintype "power_in"))
      (node (ref "GY521") (pin "7") (pinfunction "AD0_7") (pintype "input"))
      (node (ref "J1") (pin "1") (pinfunction "S_1") (pintype "passive"))
      (node (ref "JTAG") (pin "10") (pinfunction "KL_10") (pintype "passive"))
      (node (ref "JTAG") (pin "12") (pinfunction "KL_12") (pintype "passive"))
      (node (ref "JTAG") (pin "14") (pinfunction "KL_14") (pintype "passive"))
      (node (ref "JTAG") (pin "16") (pinfunction "KL_16") (pintype "passive"))
      (node (ref "JTAG") (pin "18") (pinfunction "KL_18") (pintype "passive"))
      (node (ref "JTAG") (pin "20") (pinfunction "KL_20") (pintype "passive"))
      (node (ref "JTAG") (pin "4") (pinfunction "KL_4") (pintype "passive"))
      (node (ref "JTAG") (pin "6") (pinfunction "KL_6") (pintype "passive"))
      (node (ref "JTAG") (pin "8") (pinfunction "KL_8") (pintype "passive"))
      (node (ref "LCD") (pin "8") (pinfunction "8_8") (pintype "passive"))
      (node (ref "OK2") (pin "2") (pinfunction "C_2") (pintype "passive"))
      (node (ref "OK4") (pin "2") (pinfunction "C_2") (pintype "passive"))
      (node (ref "PB8") (pin "K") (pinfunction "C_K") (pintype "passive"))
      (node (ref "R1") (pin "1") (pinfunction "1_1") (pintype "passive"))
      (node (ref "R10") (pin "1") (pinfunction "1_1") (pintype "passive"))
      (node (ref "R15") (pin "1") (pinfunction "1_1") (pintype "passive"))
      (node (ref "R17") (pin "1") (pinfunction "1_1") (pintype "passive"))
      (node (ref "R21") (pin "1") (pinfunction "1_1") (pintype "passive"))
      (node (ref "R26") (pin "1") (pinfunction "1_1") (pintype "passive"))
      (node (ref "R27") (pin "1") (pinfunction "1_1") (pintype "passive"))
      (node (ref "R28") (pin "1") (pinfunction "1_1") (pintype "passive"))
      (node (ref "R32") (pin "1") (pinfunction "1_1") (pintype "passive"))
      (node (ref "R33") (pin "1") (pinfunction "1_1") (pintype "passive"))
      (node (ref "R34") (pin "2") (pinfunction "2_2") (pintype "passive"))
      (node (ref "R36") (pin "1") (pinfunction "1_1") (pintype "passive"))
      (node (ref "R8") (pin "1") (pinfunction "1_1") (pintype "passive"))
      (node (ref "R9") (pin "1") (pinfunction "1_1") (pintype "passive"))
      (node (ref "RESET") (pin "1") (pinfunction "S_1") (pintype "passive"))
      (node (ref "RESET") (pin "2") (pinfunction "S1_2") (pintype "passive"))
      (node (ref "S1") (pin "3") (pinfunction "P_3") (pintype "passive"))
      (node (ref "S1") (pin "4") (pinfunction "P1_4") (pintype "passive"))
      (node (ref "SPI2") (pin "3") (pinfunction "3_3") (pintype "passive"))
      (node (ref "SPI2") (pin "4") (pinfunction "4_4") (pintype "passive"))
      (node (ref "SV1") (pin "6") (pinfunction "6_6") (pintype "passive"))
      (node (ref "SV10") (pin "1") (pinfunction "1_1") (pintype "passive"))
      (node (ref "SV10") (pin "2") (pinfunction "2_2") (pintype "passive"))
      (node (ref "SV11") (pin "1") (pinfunction "1_1") (pintype "passive"))
      (node (ref "SV11") (pin "2") (pinfunction "2_2") (pintype "passive"))
      (node (ref "SV12") (pin "1") (pinfunction "1_1") (pintype "passive"))
      (node (ref "SV2") (pin "2") (pinfunction "2_2") (pintype "passive"))
      (node (ref "SV3") (pin "8") (pinfunction "8_8") (pintype "passive"))
      (node (ref "SV4") (pin "5") (pinfunction "5_5") (pintype "passive"))
      (node (ref "SV5") (pin "1") (pinfunction "1_1") (pintype "passive"))
      (node (ref "SV6") (pin "1") (pinfunction "1_1") (pintype "passive"))
      (node (ref "SV7") (pin "2") (pinfunction "2_2") (pintype "passive"))
      (node (ref "SV8") (pin "1") (pinfunction "1_1") (pintype "passive"))
      (node (ref "SV8") (pin "2") (pinfunction "2_2") (pintype "passive"))
      (node (ref "SV9") (pin "1") (pinfunction "1_1") (pintype "passive"))
      (node (ref "SV9") (pin "2") (pinfunction "2_2") (pintype "passive"))
      (node (ref "SWD") (pin "3") (pinfunction "3_3") (pintype "passive"))
      (node (ref "TO_LCD") (pin "3") (pinfunction "3_3") (pintype "passive"))
      (node (ref "TO_LCD") (pin "5") (pinfunction "5_5") (pintype "passive"))
      (node (ref "U1") (pin "23") (pinfunction "VSS_23") (pintype "power_in"))
      (node (ref "U1") (pin "35") (pinfunction "VSS_35") (pintype "power_in"))
      (node (ref "U1") (pin "47") (pinfunction "VSS_47") (pintype "power_in"))
      (node (ref "U1") (pin "8") (pinfunction "VSSA_8") (pintype "power_in"))
      (node (ref "U2") (pin "1") (pinfunction "GND_1") (pintype "input"))
      (node (ref "U3") (pin "15") (pinfunction "CONFIG_15") (pintype "passive"))
      (node (ref "U3") (pin "21") (pinfunction "GND_21") (pintype "power_in"))
      (node (ref "U4") (pin "4") (pinfunction "V-_4") (pintype "power_in"))
      (node (ref "U5") (pin "4") (pinfunction "G2A_4") (pintype "input"))
      (node (ref "U5") (pin "5") (pinfunction "G2B_5") (pintype "input"))
      (node (ref "U5") (pin "8") (pinfunction "GND_8") (pintype "power_in"))
      (node (ref "UART1") (pin "1") (pinfunction "1_1") (pintype "passive"))
      (node (ref "USB") (pin "4") (pinfunction "4_4") (pintype "passive"))
      (node (ref "USB") (pin "S1") (pinfunction "S1_S1") (pintype "passive"))
      (node (ref "USB") (pin "S2") (pinfunction "S2_S2") (pintype "passive"))
      (node (ref "V+") (pin "1") (pinfunction "S_1") (pintype "passive"))
      (node (ref "WIFI") (pin "2") (pinfunction "2_2") (pintype "passive"))
    )
    (net (code "28") (name "I2C2_SCL") (class "Default")
      (node (ref "GY521") (pin "3") (pinfunction "SCL_3") (pintype "input"))
      (node (ref "R13") (pin "1") (pinfunction "1_1") (pintype "passive"))
      (node (ref "SV4") (pin "9") (pinfunction "9_9") (pintype "passive"))
      (node (ref "U1") (pin "21") (pinfunction "PB10/I2C2_SCL/USART3_TX_21") (pintype "bidirectional"))
    )
    (net (code "29") (name "I2C2_SDA") (class "Default")
      (node (ref "GY521") (pin "4") (pinfunction "SDA_4") (pintype "bidirectional"))
      (node (ref "R14") (pin "1") (pinfunction "1_1") (pintype "passive"))
      (node (ref "SV4") (pin "10") (pinfunction "10_10") (pintype "passive"))
      (node (ref "SV4") (pin "12") (pinfunction "12_12") (pintype "passive"))
      (node (ref "U1") (pin "22") (pinfunction "PB11/I2C2_SDA/USART3_RX_22") (pintype "bidirectional"))
    )
    (net (code "30") (name "Net-(C14-Pad1)") (class "Default")
      (node (ref "C14") (pin "1") (pinfunction "1_1") (pintype "passive"))
      (node (ref "C15") (pin "2") (pinfunction "2_2") (pintype "passive"))
      (node (ref "C17") (pin "+") (pinfunction "+_+") (pintype "passive"))
      (node (ref "R24") (pin "1") (pinfunction "1_1") (pintype "passive"))
      (node (ref "U3") (pin "18") (pinfunction "VM_18") (pintype "power_in"))
      (node (ref "U3") (pin "19") (pinfunction "VM_19") (pintype "power_in"))
    )
    (net (code "31") (name "Net-(D1-PadA)") (class "Default")
      (node (ref "D1") (pin "A") (pinfunction "A_A") (pintype "passive"))
      (node (ref "USB") (pin "1") (pinfunction "1_1") (pintype "passive"))
    )
    (net (code "32") (name "Net-(J3-Pad1)") (class "Default")
      (node (ref "J3") (pin "1") (pinfunction "1_1") (pintype "passive"))
      (node (ref "SV12") (pin "4") (pinfunction "4_4") (pintype "passive"))
    )
    (net (code "33") (name "Net-(LCD-Pad1)") (class "Default")
      (node (ref "LCD") (pin "1") (pinfunction "1_1") (pintype "passive"))
      (node (ref "PB14") (pin "2") (pinfunction "2_2") (pintype "passive"))
    )
    (net (code "34") (name "Net-(MOTORA-K)") (class "Default")
      (node (ref "MOTOR") (pin "1") (pinfunction "K_1") (pintype "passive"))
      (node (ref "U3") (pin "4") (pinfunction "AOUT1_4") (pintype "passive"))
    )
    (net (code "35") (name "Net-(MOTORB-K)") (class "Default")
      (node (ref "MOTOR") (pin "2") (pinfunction "K_2") (pintype "passive"))
      (node (ref "U3") (pin "6") (pinfunction "AOUT2_6") (pintype "passive"))
    )
    (net (code "36") (name "Net-(MOTORC-K)") (class "Default")
      (node (ref "MOTOR") (pin "3") (pinfunction "K_3") (pintype "passive"))
      (node (ref "U3") (pin "7") (pinfunction "BOUT2_7") (pintype "passive"))
    )
    (net (code "37") (name "Net-(MOTORD-K)") (class "Default")
      (node (ref "MOTOR") (pin "4") (pinfunction "K_4") (pintype "passive"))
      (node (ref "U3") (pin "9") (pinfunction "BOUT1_9") (pintype "passive"))
    )
    (net (code "38") (name "Net-(OK1-C)") (class "Default")
      (node (ref "OK1") (pin "2") (pinfunction "C_2") (pintype "passive"))
      (node (ref "OK3") (pin "2") (pinfunction "C_2") (pintype "passive"))
      (node (ref "R25") (pin "1") (pinfunction "1_1") (pintype "passive"))
    )
    (net (code "39") (name "Net-(OK1-EMIT)") (class "Default")
      (node (ref "OK1") (pin "4") (pinfunction "EMIT_4") (pintype "passive"))
      (node (ref "OK3") (pin "4") (pinfunction "EMIT_4") (pintype "passive"))
      (node (ref "R20") (pin "1") (pinfunction "1_1") (pintype "passive"))
      (node (ref "R26") (pin "2") (pinfunction "2_2") (pintype "passive"))
      (node (ref "SV5") (pin "3") (pinfunction "3_3") (pintype "passive"))
      (node (ref "SV6") (pin "4") (pinfunction "4_4") (pintype "passive"))
      (node (ref "SV7") (pin "3") (pinfunction "3_3") (pintype "passive"))
    )
    (net (code "40") (name "Net-(OK2-A)") (class "Default")
      (node (ref "OK2") (pin "1") (pinfunction "A_1") (pintype "passive"))
      (node (ref "OK4") (pin "1") (pinfunction "A_1") (pintype "passive"))
      (node (ref "R25") (pin "2") (pinfunction "2_2") (pintype "passive"))
    )
    (net (code "41") (name "Net-(OK2-EMIT)") (class "Default")
      (node (ref "OK2") (pin "4") (pinfunction "EMIT_4") (pintype "passive"))
      (node (ref "OK4") (pin "4") (pinfunction "EMIT_4") (pintype "passive"))
      (node (ref "R16") (pin "1") (pinfunction "1_1") (pintype "passive"))
      (node (ref "R27") (pin "2") (pinfunction "2_2") (pintype "passive"))
      (node (ref "SV6") (pin "3") (pinfunction "3_3") (pintype "passive"))
      (node (ref "SV7") (pin "4") (pinfunction "4_4") (pintype "passive"))
    )
    (net (code "42") (name "Net-(PB8-PadA)") (class "Default")
      (node (ref "PB8") (pin "A") (pinfunction "A_A") (pintype "passive"))
      (node (ref "R4") (pin "2") (pinfunction "2_2") (pintype "passive"))
    )
    (net (code "43") (name "Net-(R11-Pad1)") (class "Default")
      (node (ref "R11") (pin "1") (pinfunction "1_1") (pintype "passive"))
      (node (ref "UART1") (pin "4") (pinfunction "4_4") (pintype "passive"))
    )
    (net (code "44") (name "Net-(R18-Pad1)") (class "Default")
      (node (ref "R18") (pin "1") (pinfunction "1_1") (pintype "passive"))
      (node (ref "R19") (pin "1") (pinfunction "1_1") (pintype "passive"))
      (node (ref "R30") (pin "2") (pinfunction "2_2") (pintype "passive"))
    )
    (net (code "45") (name "Net-(R22-Pad1)") (class "Default")
      (node (ref "R22") (pin "1") (pinfunction "1_1") (pintype "passive"))
      (node (ref "R23") (pin "1") (pinfunction "1_1") (pintype "passive"))
      (node (ref "R31") (pin "2") (pinfunction "2_2") (pintype "passive"))
    )
    (net (code "46") (name "Net-(R35-Pad1)") (class "Default")
      (node (ref "R35") (pin "1") (pinfunction "1_1") (pintype "passive"))
      (node (ref "SV12") (pin "2") (pinfunction "2_2") (pintype "passive"))
    )
    (net (code "47") (name "Net-(RESET-P1)") (class "Default")
      (node (ref "R3") (pin "1") (pinfunction "1_1") (pintype "passive"))
      (node (ref "RESET") (pin "4") (pinfunction "P1_4") (pintype "passive"))
    )
    (net (code "48") (name "Net-(S1-S)") (class "Default")
      (node (ref "R2") (pin "2") (pinfunction "2_2") (pintype "passive"))
      (node (ref "R5") (pin "1") (pinfunction "1_1") (pintype "passive"))
      (node (ref "S1") (pin "1") (pinfunction "S_1") (pintype "passive"))
    )
    (net (code "49") (name "Net-(S1-S1)") (class "Default")
      (node (ref "C10") (pin "1") (pinfunction "1_1") (pintype "passive"))
      (node (ref "S1") (pin "2") (pinfunction "S1_2") (pintype "passive"))
    )
    (net (code "50") (name "Net-(U1-NRST)") (class "Default")
      (node (ref "R3") (pin "2") (pinfunction "2_2") (pintype "passive"))
      (node (ref "U1") (pin "7") (pinfunction "NRST_7") (pintype "input"))
    )
    (net (code "51") (name "Net-(U1-PA7{slash}SPI1_MOSI{slash}ADC12_IN7{slash}TIM3_CH2)") (class "Default")
      (node (ref "R7") (pin "2") (pinfunction "2_2") (pintype "passive"))
      (node (ref "U1") (pin "17") (pinfunction "PA7/SPI1_MOSI/ADC12_IN7/TIM3_CH2_17") (pintype "bidirectional"))
    )
    (net (code "52") (name "Net-(U2-IN)") (class "Default")
      (node (ref "C13") (pin "+") (pinfunction "+_+") (pintype "passive"))
      (node (ref "D1") (pin "C") (pinfunction "C_C") (pintype "passive"))
      (node (ref "D2") (pin "C") (pinfunction "C_C") (pintype "passive"))
      (node (ref "U2") (pin "3") (pinfunction "IN_3") (pintype "input"))
    )
    (net (code "53") (name "Net-(U3A-ADECAY)") (class "Default")
      (node (ref "R15") (pin "2") (pinfunction "2_2") (pintype "passive"))
      (node (ref "U3") (pin "3") (pinfunction "ADECAY_3") (pintype "passive"))
    )
    (net (code "54") (name "Net-(U3A-AISEN)") (class "Default")
      (node (ref "R8") (pin "2") (pinfunction "2_2") (pintype "passive"))
      (node (ref "U3") (pin "5") (pinfunction "AISEN_5") (pintype "passive"))
    )
    (net (code "55") (name "Net-(U3A-AVREF)") (class "Default")
      (node (ref "U3") (pin "22") (pinfunction "AVREF_22") (pintype "passive"))
      (node (ref "U3") (pin "23") (pinfunction "BVREF_23") (pintype "passive"))
      (node (ref "U3") (pin "24") (pinfunction "VREFO_24") (pintype "passive"))
    )
    (net (code "56") (name "Net-(U3A-BDECAY)") (class "Default")
      (node (ref "R10") (pin "2") (pinfunction "2_2") (pintype "passive"))
      (node (ref "U3") (pin "2") (pinfunction "BDECAY_2") (pintype "passive"))
    )
    (net (code "57") (name "Net-(U3A-BISEN)") (class "Default")
      (node (ref "R9") (pin "2") (pinfunction "2_2") (pintype "passive"))
      (node (ref "U3") (pin "8") (pinfunction "BISEN_8") (pintype "passive"))
    )
    (net (code "58") (name "Net-(U3A-VCP)") (class "Default")
      (node (ref "C15") (pin "1") (pinfunction "1_1") (pintype "passive"))
      (node (ref "U3") (pin "17") (pinfunction "VCP_17") (pintype "passive"))
    )
    (net (code "59") (name "Net-(U3A-VINT)") (class "Default")
      (node (ref "C16") (pin "1") (pinfunction "1_1") (pintype "passive"))
      (node (ref "U3") (pin "20") (pinfunction "VINT_20") (pintype "passive"))
    )
    (net (code "60") (name "Net-(U4A-+IN)") (class "Default")
      (node (ref "R21") (pin "2") (pinfunction "2_2") (pintype "passive"))
      (node (ref "R31") (pin "1") (pinfunction "1_1") (pintype "passive"))
      (node (ref "U4") (pin "3") (pinfunction "+IN_3") (pintype "input"))
    )
    (net (code "61") (name "Net-(U4A--IN)") (class "Default")
      (node (ref "C20") (pin "1") (pinfunction "1_1") (pintype "passive"))
      (node (ref "R16") (pin "2") (pinfunction "2_2") (pintype "passive"))
      (node (ref "U4") (pin "2") (pinfunction "-IN_2") (pintype "input"))
    )
    (net (code "62") (name "Net-(U4B-+IN)") (class "Default")
      (node (ref "R17") (pin "2") (pinfunction "2_2") (pintype "passive"))
      (node (ref "R30") (pin "1") (pinfunction "1_1") (pintype "passive"))
      (node (ref "U4") (pin "5") (pinfunction "+IN_5") (pintype "input"))
    )
    (net (code "63") (name "Net-(U4B--IN)") (class "Default")
      (node (ref "C19") (pin "1") (pinfunction "1_1") (pintype "passive"))
      (node (ref "R20") (pin "2") (pinfunction "2_2") (pintype "passive"))
      (node (ref "U4") (pin "6") (pinfunction "-IN_6") (pintype "input"))
    )
    (net (code "64") (name "Net-(U4B-OUT)") (class "Default")
      (node (ref "J2") (pin "1") (pinfunction "1_1") (pintype "passive"))
      (node (ref "R18") (pin "2") (pinfunction "2_2") (pintype "passive"))
      (node (ref "U4") (pin "7") (pinfunction "OUT_7") (pintype "output"))
    )
    (net (code "65") (name "Net-(U5A-A)") (class "Default")
      (node (ref "R34") (pin "1") (pinfunction "1_1") (pintype "passive"))
      (node (ref "TO_LCD") (pin "1") (pinfunction "1_1") (pintype "passive"))
      (node (ref "U5") (pin "1") (pinfunction "A_1") (pintype "input"))
    )
    (net (code "66") (name "Net-(U5A-C)") (class "Default")
      (node (ref "R32") (pin "2") (pinfunction "2_2") (pintype "passive"))
      (node (ref "TO_LCD") (pin "6") (pinfunction "6_6") (pintype "passive"))
      (node (ref "U5") (pin "3") (pinfunction "C_3") (pintype "input"))
    )
    (net (code "67") (name "Net-(U5A-Y0)") (class "Default")
      (node (ref "SV8") (pin "6") (pinfunction "6_6") (pintype "passive"))
      (node (ref "U5") (pin "15") (pinfunction "Y0_15") (pintype "output"))
    )
    (net (code "68") (name "Net-(U5A-Y1)") (class "Default")
      (node (ref "SV9") (pin "5") (pinfunction "5_5") (pintype "passive"))
      (node (ref "U5") (pin "14") (pinfunction "Y1_14") (pintype "output"))
    )
    (net (code "69") (name "Net-(U5A-Y2)") (class "Default")
      (node (ref "SV9") (pin "6") (pinfunction "6_6") (pintype "passive"))
      (node (ref "U5") (pin "13") (pinfunction "Y2_13") (pintype "output"))
    )
    (net (code "70") (name "Net-(U5A-Y3)") (class "Default")
      (node (ref "SV10") (pin "5") (pinfunction "5_5") (pintype "passive"))
      (node (ref "U5") (pin "12") (pinfunction "Y3_12") (pintype "output"))
    )
    (net (code "71") (name "Net-(U5A-Y4)") (class "Default")
      (node (ref "SV10") (pin "6") (pinfunction "6_6") (pintype "passive"))
      (node (ref "U5") (pin "11") (pinfunction "Y4_11") (pintype "output"))
    )
    (net (code "72") (name "Net-(U5A-Y5)") (class "Default")
      (node (ref "SV11") (pin "5") (pinfunction "5_5") (pintype "passive"))
      (node (ref "U5") (pin "10") (pinfunction "Y5_10") (pintype "output"))
    )
    (net (code "73") (name "Net-(U5A-Y6)") (class "Default")
      (node (ref "SV11") (pin "6") (pinfunction "6_6") (pintype "passive"))
      (node (ref "U5") (pin "9") (pinfunction "Y6_9") (pintype "output"))
    )
    (net (code "74") (name "Net-(U5A-Y7)") (class "Default")
      (node (ref "SV8") (pin "5") (pinfunction "5_5") (pintype "passive"))
      (node (ref "U5") (pin "7") (pinfunction "Y7_7") (pintype "output"))
    )
    (net (code "75") (name "PA0") (class "Default")
      (node (ref "SV3") (pin "10") (pinfunction "10_10") (pintype "passive"))
      (node (ref "U1") (pin "10") (pinfunction "PA0/WKUP/USART2_CTS/ADC12_IN0/TIM2_CH1_ETR_10") (pintype "bidirectional"))
      (node (ref "U3") (pin "12") (pinfunction "DIR/BPHASE_12") (pintype "passive"))
    )
    (net (code "76") (name "PA8") (class "Default")
      (node (ref "GY521") (pin "8") (pinfunction "INT_8") (pintype "output"))
      (node (ref "SV1") (pin "7") (pinfunction "7_7") (pintype "passive"))
      (node (ref "U1") (pin "29") (pinfunction "USART1_CK/TIM1_CH1/MCO/PA8_29") (pintype "bidirectional"))
    )
    (net (code "77") (name "PC14") (class "Default")
      (node (ref "SV3") (pin "3") (pinfunction "3_3") (pintype "passive"))
      (node (ref "U1") (pin "3") (pinfunction "PC14/OSC32_IN_3") (pintype "bidirectional"))
      (node (ref "U3") (pin "14") (pinfunction "M1_14") (pintype "passive"))
    )
    (net (code "78") (name "PC15") (class "Default")
      (node (ref "SV3") (pin "6") (pinfunction "6_6") (pintype "passive"))
      (node (ref "U1") (pin "4") (pinfunction "PC15/OSC32_OUT_4") (pintype "bidirectional"))
      (node (ref "U3") (pin "13") (pinfunction "M0/APHASE_13") (pintype "passive"))
    )
    (net (code "79") (name "SPI2_MISO") (class "Default")
      (node (ref "PB14") (pin "1") (pinfunction "1_1") (pintype "passive"))
      (node (ref "SPI2") (pin "8") (pinfunction "8_8") (pintype "passive"))
      (node (ref "SV1") (pin "9") (pinfunction "9_9") (pintype "passive"))
      (node (ref "U1") (pin "27") (pinfunction "SPI2_MISO/USART3_RTS/TIM1_CH2N/PB14_27") (pintype "bidirectional"))
    )
    (net (code "80") (name "SPI2_MOSI") (class "Default")
      (node (ref "LCD") (pin "4") (pinfunction "4_4") (pintype "passive"))
      (node (ref "SPI2") (pin "6") (pinfunction "6_6") (pintype "passive"))
      (node (ref "SV1") (pin "10") (pinfunction "10_10") (pintype "passive"))
      (node (ref "U1") (pin "28") (pinfunction "SPI2_MOSI/TIM1_CH3N/PB15_28") (pintype "bidirectional"))
    )
    (net (code "81") (name "SPI2_NSS") (class "Default")
      (node (ref "LCD") (pin "7") (pinfunction "7_7") (pintype "passive"))
      (node (ref "SPI2") (pin "10") (pinfunction "10_10") (pintype "passive"))
      (node (ref "SV1") (pin "11") (pinfunction "11_11") (pintype "passive"))
      (node (ref "U1") (pin "25") (pinfunction "SPI2_NSS/I2C2_SMBAI/USART3_CK/TIM1_BKIN/PB12_25") (pintype "bidirectional"))
    )
    (net (code "82") (name "SPI2_SCK") (class "Default")
      (node (ref "LCD") (pin "3") (pinfunction "3_3") (pintype "passive"))
      (node (ref "SPI2") (pin "2") (pinfunction "2_2") (pintype "passive"))
      (node (ref "SV1") (pin "12") (pinfunction "12_12") (pintype "passive"))
      (node (ref "U1") (pin "26") (pinfunction "SPI2_SCK/USART3_CTS/TIM1_CH1N/PB13_26") (pintype "bidirectional"))
    )
    (net (code "83") (name "TIM2_CH2") (class "Default")
      (node (ref "J2") (pin "2") (pinfunction "2_2") (pintype "passive"))
      (node (ref "SV3") (pin "12") (pinfunction "12_12") (pintype "passive"))
      (node (ref "U1") (pin "11") (pinfunction "PA1/USART2_RTS/ADC12_IN1/TIM2_CH2_11") (pintype "bidirectional"))
    )
    (net (code "84") (name "TIM3_CH1") (class "Default")
      (node (ref "SV4") (pin "3") (pinfunction "3_3") (pintype "passive"))
      (node (ref "U1") (pin "16") (pinfunction "PA6/SPI1_MISO/ADC12_IN6/TIM3_CH1_16") (pintype "bidirectional"))
      (node (ref "U3") (pin "10") (pinfunction "NENBL/AENBL_10") (pintype "passive"))
    )
    (net (code "85") (name "TIM3_CH2") (class "Default")
      (node (ref "R7") (pin "1") (pinfunction "1_1") (pintype "passive"))
      (node (ref "SV3") (pin "11") (pinfunction "11_11") (pintype "passive"))
      (node (ref "U3") (pin "11") (pinfunction "STEP/BENBL_11") (pintype "passive"))
    )
    (net (code "86") (name "TIM3_CH3") (class "Default")
      (node (ref "SV4") (pin "4") (pinfunction "4_4") (pintype "passive"))
      (node (ref "U1") (pin "18") (pinfunction "PB0/ADC12_IN8/TIM3_CH3_18") (pintype "bidirectional"))
      (node (ref "U5") (pin "6") (pinfunction "G1_6") (pintype "input"))
    )
    (net (code "87") (name "USART2_RX") (class "Default")
      (node (ref "U1") (pin "13") (pinfunction "PA3/USART2_RX/ADC12_IN3/TIM2_CH4_13") (pintype "bidirectional"))
      (node (ref "WIFI") (pin "1") (pinfunction "1_1") (pintype "passive"))
    )
    (net (code "88") (name "USART2_TX") (class "Default")
      (node (ref "U1") (pin "12") (pinfunction "PA2/USART2_TX/ADC12_IN2/TIM2_CH3_12") (pintype "bidirectional"))
      (node (ref "WIFI") (pin "8") (pinfunction "8_8") (pintype "passive"))
    )
    (net (code "89") (name "Vmotor+") (class "Default")
      (node (ref "D3") (pin "C") (pinfunction "C_C") (pintype "passive"))
      (node (ref "J1") (pin "3") (pinfunction "S_3") (pintype "passive"))
      (node (ref "R24") (pin "2") (pinfunction "2_2") (pintype "passive"))
    )
    (net (code "90") (name "unconnected-(GY521-XCL-Pad6)") (class "Default")
      (node (ref "GY521") (pin "6") (pinfunction "XCL_6") (pintype "output"))
    )
    (net (code "91") (name "unconnected-(GY521-XDA-Pad5)") (class "Default")
      (node (ref "GY521") (pin "5") (pinfunction "XDA_5") (pintype "bidirectional"))
    )
    (net (code "92") (name "unconnected-(JTAGC-KL-Pad11)") (class "Default")
      (node (ref "JTAG") (pin "11") (pinfunction "KL_11") (pintype "passive"))
    )
    (net (code "93") (name "unconnected-(JTAGI-KL-Pad17)") (class "Default")
      (node (ref "JTAG") (pin "17") (pinfunction "KL_17") (pintype "passive"))
    )
    (net (code "94") (name "unconnected-(JTAGK-KL-Pad19)") (class "Default")
      (node (ref "JTAG") (pin "19") (pinfunction "KL_19") (pintype "passive"))
    )
    (net (code "95") (name "unconnected-(SPI2-Pad1)") (class "Default")
      (node (ref "SPI2") (pin "1") (pinfunction "1_1") (pintype "passive"))
    )
    (net (code "96") (name "unconnected-(SPI2-Pad5)") (class "Default")
      (node (ref "SPI2") (pin "5") (pinfunction "5_5") (pintype "passive"))
    )
    (net (code "97") (name "unconnected-(SPI2-Pad7)") (class "Default")
      (node (ref "SPI2") (pin "7") (pinfunction "7_7") (pintype "passive"))
    )
    (net (code "98") (name "unconnected-(SPI2-Pad9)") (class "Default")
      (node (ref "SPI2") (pin "9") (pinfunction "9_9") (pintype "passive"))
    )
    (net (code "99") (name "unconnected-(SV3-Pad1)") (class "Default")
      (node (ref "SV3") (pin "1") (pinfunction "1_1") (pintype "passive"))
    )
    (net (code "100") (name "unconnected-(SV3-Pad5)") (class "Default")
      (node (ref "SV3") (pin "5") (pinfunction "5_5") (pintype "passive"))
    )
    (net (code "101") (name "unconnected-(SV4-Pad11)") (class "Default")
      (node (ref "SV4") (pin "11") (pinfunction "11_11") (pintype "passive"))
    )
    (net (code "102") (name "unconnected-(SWD-Pad6)") (class "Default")
      (node (ref "SWD") (pin "6") (pinfunction "6_6") (pintype "passive"))
    )
    (net (code "103") (name "unconnected-(U3A-NFAULT-Pad16)") (class "Default")
      (node (ref "U3") (pin "16") (pinfunction "NFAULT_16") (pintype "passive"))
    )
    (net (code "104") (name "unconnected-(WIFI-Pad4)") (class "Default")
      (node (ref "WIFI") (pin "4") (pinfunction "4_4") (pintype "passive"))
    )
    (net (code "105") (name "unconnected-(WIFI-Pad5)") (class "Default")
      (node (ref "WIFI") (pin "5") (pinfunction "5_5") (pintype "passive"))
    )
    (net (code "106") (name "unconnected-(WIFI-Pad6)") (class "Default")
      (node (ref "WIFI") (pin "6") (pinfunction "6_6") (pintype "passive"))
    )
  )
)
